# pc_heartypatch.net
KiCad netlist of a schematic drawn in EAGLE
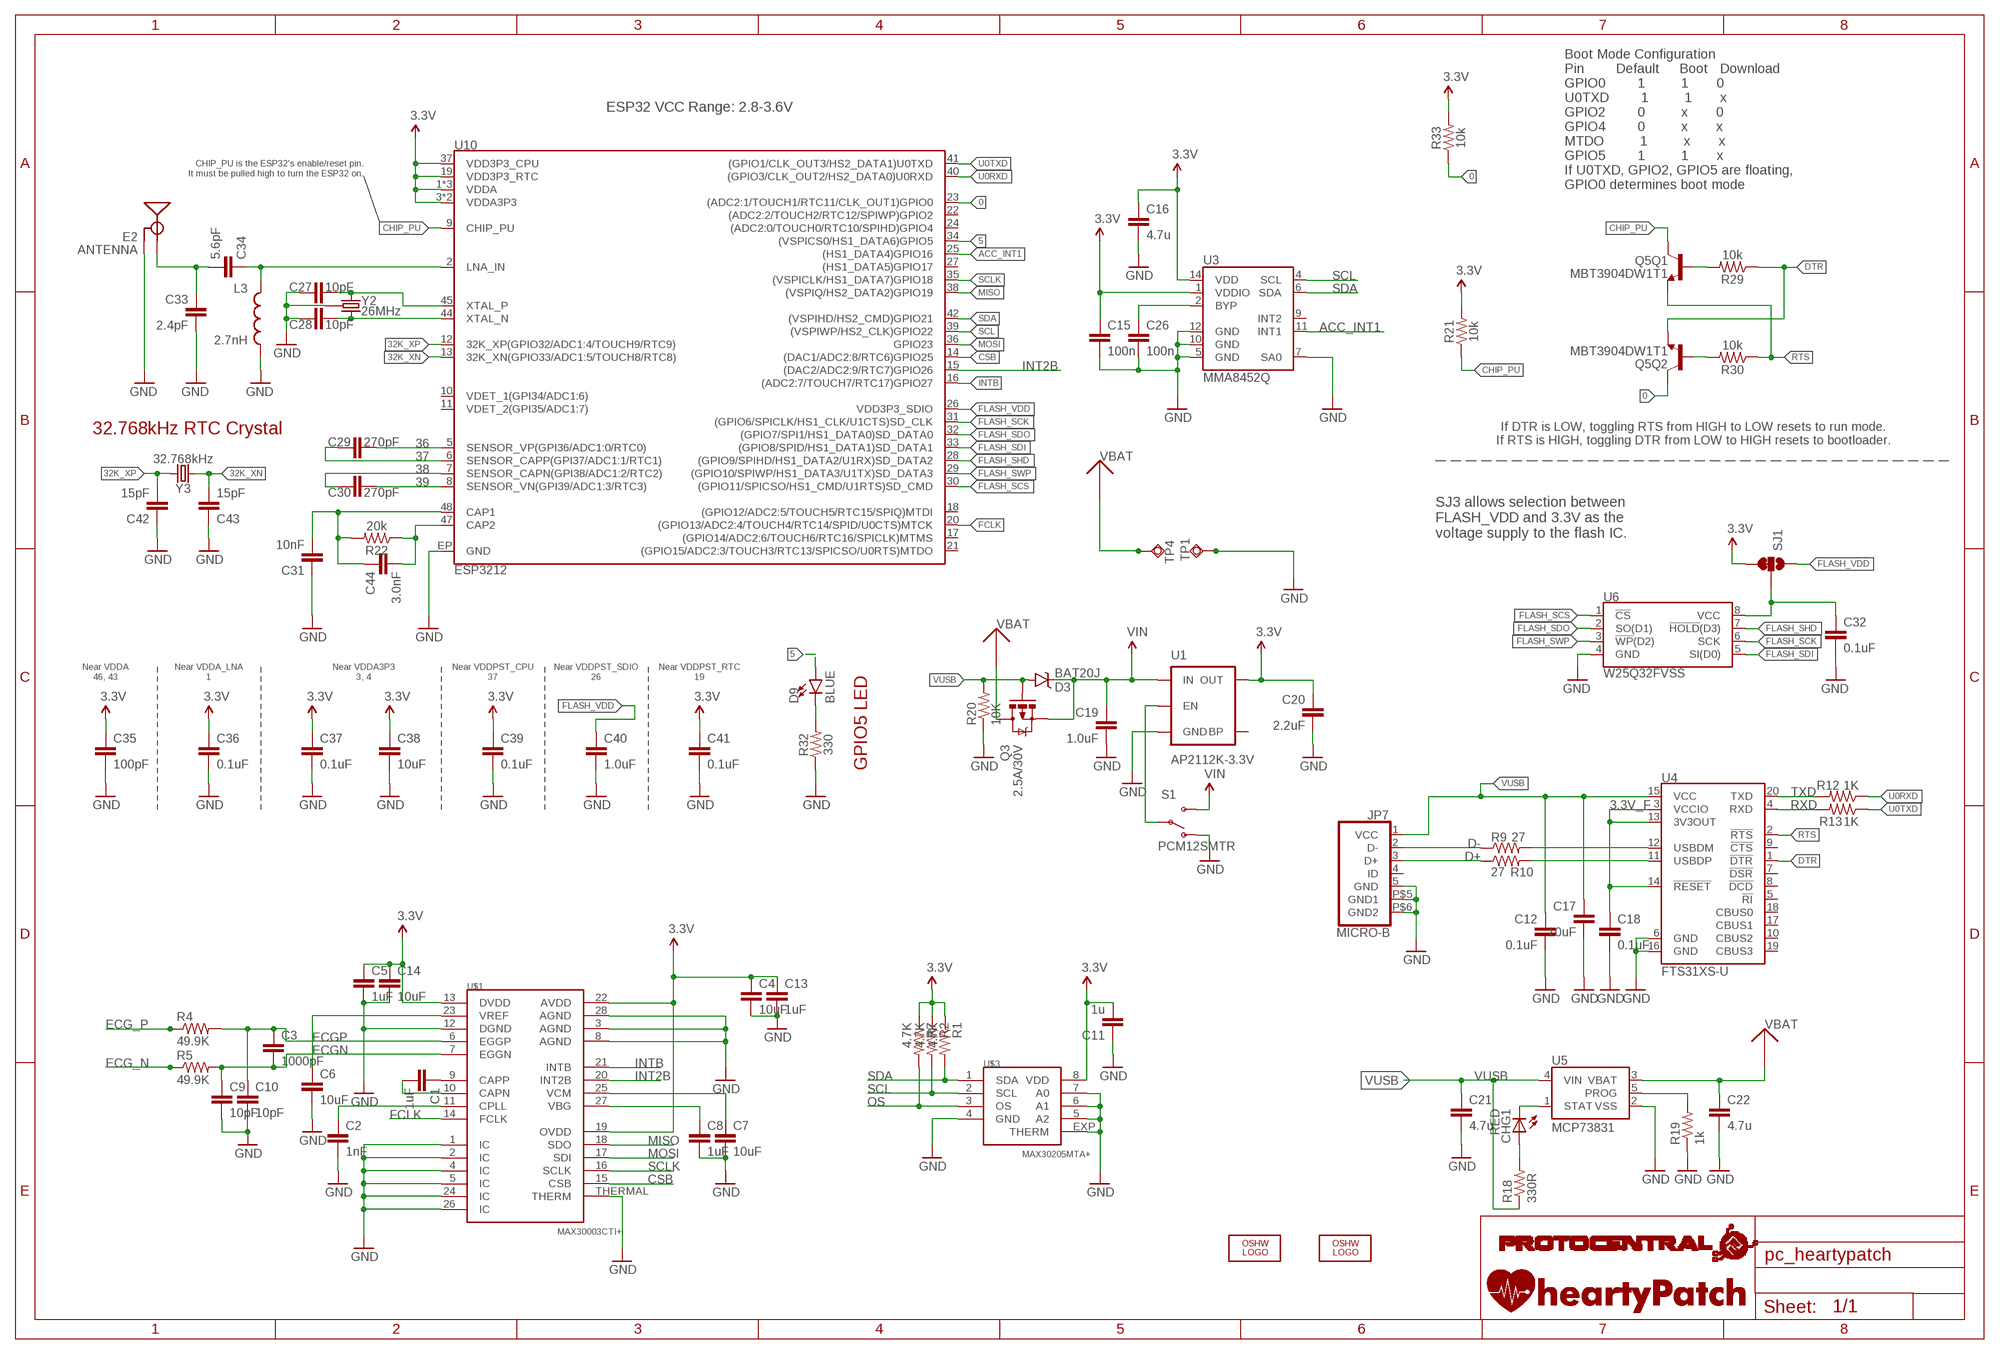
[diagram p0: schematic, sheet 1]

(export (version "E")
  (design (tool "Eeschema 10.0.6"))
  (components
    (comp (ref "C1")
      (value "1uF")
      (footprint "eagle-import:C0603")
      (libsource (lib "eagle-import") (part "C-EUC0603"))
    )
    (comp (ref "C2")
      (value "1nF")
      (footprint "eagle-import:C0603")
      (libsource (lib "eagle-import") (part "C-EUC0603"))
    )
    (comp (ref "C3")
      (value "1000pF")
      (footprint "eagle-import:C0402")
      (libsource (lib "eagle-import") (part "C-EUC0402"))
    )
    (comp (ref "C4")
      (value "10uF")
      (footprint "eagle-import:C0805")
      (libsource (lib "eagle-import") (part "C-EUC0805"))
    )
    (comp (ref "C5")
      (value "1uF")
      (footprint "eagle-import:C0402")
      (libsource (lib "eagle-import") (part "C-EUC0402"))
    )
    (comp (ref "C6")
      (value "10uF")
      (footprint "eagle-import:C0805")
      (libsource (lib "eagle-import") (part "C-EUC0805"))
    )
    (comp (ref "C7")
      (value "10uF")
      (footprint "eagle-import:C0805")
      (libsource (lib "eagle-import") (part "C-EUC0805"))
    )
    (comp (ref "C8")
      (value "1uF")
      (footprint "eagle-import:C0805")
      (libsource (lib "eagle-import") (part "C-EUC0805"))
    )
    (comp (ref "C9")
      (value "10pF")
      (footprint "eagle-import:C0402")
      (libsource (lib "eagle-import") (part "C-EUC0402"))
    )
    (comp (ref "C10")
      (value "10pF")
      (footprint "eagle-import:C0402")
      (libsource (lib "eagle-import") (part "C-EUC0402"))
    )
    (comp (ref "C11")
      (value "1u")
      (footprint "eagle-import:C0805")
      (libsource (lib "eagle-import") (part "C-EUC0805"))
    )
    (comp (ref "C12")
      (value "0.1uF")
      (footprint "eagle-import:C0402")
      (libsource (lib "eagle-import") (part "C-EUC0402"))
    )
    (comp (ref "C13")
      (value "1uF")
      (footprint "eagle-import:C0805")
      (libsource (lib "eagle-import") (part "C-EUC0805"))
    )
    (comp (ref "C14")
      (value "10uF")
      (footprint "eagle-import:C0603")
      (libsource (lib "eagle-import") (part "C-EUC0603"))
    )
    (comp (ref "C15")
      (value "100n")
      (footprint "eagle-import:C0402")
      (libsource (lib "eagle-import") (part "C-EUC0402"))
    )
    (comp (ref "C16")
      (value "4.7u")
      (footprint "eagle-import:C0805")
      (libsource (lib "eagle-import") (part "C-EUC0805"))
    )
    (comp (ref "C17")
      (value "10uF")
      (footprint "eagle-import:C0805")
      (libsource (lib "eagle-import") (part "C-EUC0805"))
    )
    (comp (ref "C18")
      (value "0.1uF")
      (footprint "eagle-import:C0402")
      (libsource (lib "eagle-import") (part "C-EUC0402"))
    )
    (comp (ref "C19")
      (value "1.0uF")
      (footprint "eagle-import:C0402")
      (libsource (lib "eagle-import") (part "C-EUC0402"))
    )
    (comp (ref "C20")
      (value "2.2uF")
      (footprint "eagle-import:0603-CAP@1")
      (libsource (lib "eagle-import") (part "2.2UF-10V-20%(0603)"))
    )
    (comp (ref "C21")
      (value "4.7u")
      (footprint "eagle-import:C0805")
      (libsource (lib "eagle-import") (part "C-EUC0805"))
    )
    (comp (ref "C22")
      (value "4.7u")
      (footprint "eagle-import:C0805")
      (libsource (lib "eagle-import") (part "C-EUC0805"))
    )
    (comp (ref "C26")
      (value "100n")
      (footprint "eagle-import:C0402")
      (libsource (lib "eagle-import") (part "C-EUC0402"))
    )
    (comp (ref "C27")
      (value "10pF")
      (footprint "eagle-import:0603")
      (libsource (lib "eagle-import") (part "10PF-0603-50V-5%"))
    )
    (comp (ref "C28")
      (value "10pF")
      (footprint "eagle-import:0603")
      (libsource (lib "eagle-import") (part "10PF-0603-50V-5%"))
    )
    (comp (ref "C29")
      (value "270pF")
      (footprint "eagle-import:0603")
      (libsource (lib "eagle-import") (part "270PF-50V-5%(0603)"))
    )
    (comp (ref "C30")
      (value "270pF")
      (footprint "eagle-import:0603")
      (libsource (lib "eagle-import") (part "270PF-50V-5%(0603)"))
    )
    (comp (ref "C31")
      (value "10nF")
      (footprint "eagle-import:0603")
      (libsource (lib "eagle-import") (part "10NF-0603-50V-10%"))
    )
    (comp (ref "C32")
      (value "0.1uF")
      (footprint "eagle-import:0402")
      (libsource (lib "eagle-import") (part "0.1UF-0402-16V-10%"))
    )
    (comp (ref "C33")
      (value "2.4pF")
      (footprint "eagle-import:0603")
      (libsource (lib "eagle-import") (part "2.4PF-0603-50V-5%"))
    )
    (comp (ref "C34")
      (value "5.6pF")
      (footprint "eagle-import:0603")
      (libsource (lib "eagle-import") (part "5.6PF-50V-5%(0603)"))
    )
    (comp (ref "C35")
      (value "100pF")
      (footprint "eagle-import:0603")
      (libsource (lib "eagle-import") (part "100PF-0603-50V-5%"))
    )
    (comp (ref "C36")
      (value "0.1uF")
      (footprint "eagle-import:0603")
      (libsource (lib "eagle-import") (part "0.1UF-0603-25V-(+80/-20%)"))
    )
    (comp (ref "C37")
      (value "0.1uF")
      (footprint "eagle-import:0603")
      (libsource (lib "eagle-import") (part "0.1UF-0603-25V-(+80/-20%)"))
    )
    (comp (ref "C38")
      (value "10uF")
      (footprint "eagle-import:0603")
      (libsource (lib "eagle-import") (part "10UF-0603-6.3V-20%"))
    )
    (comp (ref "C39")
      (value "0.1uF")
      (footprint "eagle-import:0402")
      (libsource (lib "eagle-import") (part "0.1UF-0402-16V-10%"))
    )
    (comp (ref "C40")
      (value "1.0uF")
      (footprint "eagle-import:0603")
      (libsource (lib "eagle-import") (part "1.0UF-0603-16V-10%"))
    )
    (comp (ref "C41")
      (value "0.1uF")
      (footprint "eagle-import:0603")
      (libsource (lib "eagle-import") (part "0.1UF-0603-25V-(+80/-20%)"))
    )
    (comp (ref "C42")
      (value "15pF")
      (footprint "eagle-import:0603")
      (libsource (lib "eagle-import") (part "15PF-0603-50V-5%"))
    )
    (comp (ref "C43")
      (value "15pF")
      (footprint "eagle-import:0603")
      (libsource (lib "eagle-import") (part "15PF-0603-50V-5%"))
    )
    (comp (ref "C44")
      (value "3.0nF")
      (footprint "eagle-import:0603")
      (libsource (lib "eagle-import") (part "3.0NF-0603-50V-5%"))
    )
    (comp (ref "CHG1")
      (value "RED")
      (footprint "eagle-import:CHIPLED_0603")
      (libsource (lib "eagle-import") (part "LEDCHIPLED_0603"))
    )
    (comp (ref "D3")
      (value "BAT20J")
      (footprint "eagle-import:SOD-323")
      (libsource (lib "eagle-import") (part "DIODE-SCHOTTKY-BAT20J"))
    )
    (comp (ref "D9")
      (value "BLUE")
      (footprint "eagle-import:LED-0603")
      (libsource (lib "eagle-import") (part "LED-BLUE0603"))
    )
    (comp (ref "E2")
      (value "ANTENNA")
      (footprint "eagle-import:TRACE_ANTENNA_2.4GHZ_25.7MM_TUNED")
      (libsource (lib "eagle-import") (part "ANTENNATRACE-TUNED"))
    )
    (comp (ref "JP7")
      (value "MICRO-B")
      (footprint "eagle-import:MICRO-B")
      (libsource (lib "eagle-import") (part "MICRO-B"))
    )
    (comp (ref "L3")
      (value "2.7nH")
      (footprint "eagle-import:0603")
      (libsource (lib "eagle-import") (part "INDUCTOR0603"))
    )
    (comp (ref "LOGO1")
      (value "OSHW_LOGO_FILLX0200-NT")
      (footprint "eagle-import:OSHW_FILLX200_NOTEXT")
      (libsource (lib "eagle-import") (part "OSHW_LOGO_FILLX0200-NT"))
    )
    (comp (ref "LOGO2")
      (value "OSHW_LOGO_FILLX0200-NT")
      (footprint "eagle-import:OSHW_FILLX200_NOTEXT")
      (libsource (lib "eagle-import") (part "OSHW_LOGO_FILLX0200-NT"))
    )
    (comp (ref "Q3")
      (value "2.5A/30V")
      (footprint "eagle-import:SOT23-3")
      (libsource (lib "eagle-import") (part "MOSFET-PCHANNELDMG2307L"))
    )
    (comp (ref "Q5")
      (value "MBT3904DW1T1")
      (footprint "eagle-import:SC70-6")
      (libsource (lib "eagle-import") (part "MBT3904DW1T1"))
    )
    (comp (ref "R1")
      (value "4.7K")
      (footprint "eagle-import:R0402")
      (libsource (lib "eagle-import") (part "R-US_R0402"))
    )
    (comp (ref "R2")
      (value "4.7K")
      (footprint "eagle-import:R0402")
      (libsource (lib "eagle-import") (part "R-US_R0402"))
    )
    (comp (ref "R4")
      (value "49.9K")
      (footprint "eagle-import:0805")
      (libsource (lib "eagle-import") (part "RESISTOR0805-RES"))
    )
    (comp (ref "R5")
      (value "49.9K")
      (footprint "eagle-import:0805")
      (libsource (lib "eagle-import") (part "RESISTOR0805-RES"))
    )
    (comp (ref "R7")
      (value "4.7K")
      (footprint "eagle-import:R0402")
      (libsource (lib "eagle-import") (part "R-US_R0402"))
    )
    (comp (ref "R9")
      (value "27")
      (footprint "eagle-import:R0402")
      (libsource (lib "eagle-import") (part "R-US_R0402"))
    )
    (comp (ref "R10")
      (value "27")
      (footprint "eagle-import:R0402")
      (libsource (lib "eagle-import") (part "R-US_R0402"))
    )
    (comp (ref "R12")
      (value "1K")
      (footprint "eagle-import:R0402")
      (libsource (lib "eagle-import") (part "R-US_R0402"))
    )
    (comp (ref "R13")
      (value "1K")
      (footprint "eagle-import:R0402")
      (libsource (lib "eagle-import") (part "R-US_R0402"))
    )
    (comp (ref "R18")
      (value "330R")
      (footprint "eagle-import:R0402")
      (libsource (lib "eagle-import") (part "R-US_R0402"))
    )
    (comp (ref "R19")
      (value "1k")
      (footprint "eagle-import:R0402")
      (libsource (lib "eagle-import") (part "R-US_R0402"))
    )
    (comp (ref "R20")
      (value "10K")
      (footprint "eagle-import:R0402")
      (libsource (lib "eagle-import") (part "R-US_R0402"))
    )
    (comp (ref "R21")
      (value "10k")
      (footprint "eagle-import:0603")
      (libsource (lib "eagle-import") (part "10KOHM-1/10W-1%(0603)0603"))
    )
    (comp (ref "R22")
      (value "20k")
      (footprint "eagle-import:0603")
      (libsource (lib "eagle-import") (part "20KOHM-0603-1/10W-1%"))
    )
    (comp (ref "R29")
      (value "10k")
      (footprint "eagle-import:0603")
      (libsource (lib "eagle-import") (part "10KOHM-0603-1/10W-1%"))
    )
    (comp (ref "R30")
      (value "10k")
      (footprint "eagle-import:0603")
      (libsource (lib "eagle-import") (part "10KOHM-0603-1/10W-1%"))
    )
    (comp (ref "R32")
      (value "330")
      (footprint "eagle-import:0603")
      (libsource (lib "eagle-import") (part "330OHM1/10W1%(0603)"))
    )
    (comp (ref "R33")
      (value "10k")
      (footprint "eagle-import:0603")
      (libsource (lib "eagle-import") (part "10KOHM-1/10W-1%(0603)0603"))
    )
    (comp (ref "S1")
      (value "PCM12SMTR")
      (footprint "eagle-import:SWITCH-SPST-SMD-A")
      (libsource (lib "eagle-import") (part "SWITCH-SPDT-SMD-A"))
    )
    (comp (ref "SJ1")
      (value "JUMPER-PAD-3-2OF3_NC_BY_TRACE_SMALL")
      (footprint "eagle-import:PAD-JUMPER-3-2OF3_NC_BY_TRACE_YES_SILK_FULL_BOX")
      (libsource (lib "eagle-import") (part "JUMPER-PAD-3-2OF3_NC_BY_TRACE_SMALL"))
    )
    (comp (ref "TP1")
      (value "TPSQTP20SQ")
      (footprint "eagle-import:TP20SQ")
      (libsource (lib "eagle-import") (part "TPSQTP20SQ"))
    )
    (comp (ref "TP4")
      (value "TPSQTP20SQ")
      (footprint "eagle-import:TP20SQ")
      (libsource (lib "eagle-import") (part "TPSQTP20SQ"))
    )
    (comp (ref "U$1")
      (value "MAX30003CTI+")
      (footprint "eagle-import:QFN-28")
      (libsource (lib "eagle-import") (part "MAX30003"))
    )
    (comp (ref "U$3")
      (value "MAX30205MTA+")
      (footprint "eagle-import:TDFN-08")
      (libsource (lib "eagle-import") (part "MAX30205MTA+"))
    )
    (comp (ref "U$8")
      (value "HEARTYPATCHHEART")
      (footprint "eagle-import:HEARTYPATCH")
      (libsource (lib "eagle-import") (part "HEARTYPATCHHEART"))
    )
    (comp (ref "U$9")
      (value "PROTY_LOGO_WITH_TEXT")
      (footprint "eagle-import:PROTY_WITH_TEXT")
      (libsource (lib "eagle-import") (part "PROTY_LOGO_WITH_TEXT"))
    )
    (comp (ref "U1")
      (value "AP2112K-3.3V")
      (footprint "eagle-import:SOT23-5")
      (libsource (lib "eagle-import") (part "V_REG_LDOSMD"))
    )
    (comp (ref "U3")
      (value "MMA8452Q")
      (footprint "eagle-import:QFN-16_0.5MM")
      (libsource (lib "eagle-import") (part "MMA8452Q"))
    )
    (comp (ref "U4")
      (value "FTS31XS-U")
      (footprint "eagle-import:SSOP20_L")
      (libsource (lib "eagle-import") (part "FT231XS"))
    )
    (comp (ref "U5")
      (value "MCP73831")
      (footprint "eagle-import:SOT23-5")
      (libsource (lib "eagle-import") (part "MCP73831"))
    )
    (comp (ref "U6")
      (value "W25Q32FVSS")
      (footprint "eagle-import:SOIC-8")
      (libsource (lib "eagle-import") (part "W25Q32FVSS"))
    )
    (comp (ref "U10")
      (value "ESP3212")
      (footprint "eagle-import:QFN48-0.4MM")
      (libsource (lib "eagle-import") (part "ESP3212"))
    )
    (comp (ref "Y2")
      (value "26MHz")
      (footprint "eagle-import:CRYSTAL-SMD-3.2X2.5")
      (libsource (lib "eagle-import") (part "CRYSTAL-GROUNDED3.2X2.5"))
    )
    (comp (ref "Y3")
      (value "32.768kHz")
      (footprint "eagle-import:CRYSTAL-SMD-3.2X1.5MM")
      (libsource (lib "eagle-import") (part "CRYSTAL-32.768KHZSMD-3.2X1.5"))
    )
  )
  (nets
    (net (code "1") (name "/3.3V_F") (class "Default")
      (node (ref "C18") (pin "1") (pinfunction "1_1") (pintype "passive"))
      (node (ref "U4") (pin "13") (pinfunction "3V3OUT_13") (pintype "bidirectional"))
      (node (ref "U4") (pin "14") (pinfunction "~{RESET}_14") (pintype "bidirectional"))
      (node (ref "U4") (pin "3") (pinfunction "VCCIO_3") (pintype "bidirectional"))
    )
    (net (code "2") (name "/36") (class "Default")
      (node (ref "C29") (pin "2") (pinfunction "2_2") (pintype "passive"))
      (node (ref "U10") (pin "5") (pinfunction "SENSOR_VP(GPI36/ADC1:0/RTC0)_5") (pintype "bidirectional"))
    )
    (net (code "3") (name "/37") (class "Default")
      (node (ref "C29") (pin "1") (pinfunction "1_1") (pintype "passive"))
      (node (ref "U10") (pin "6") (pinfunction "SENSOR_CAPP(GPI37/ADC1:1/RTC1)_6") (pintype "bidirectional"))
    )
    (net (code "4") (name "/38") (class "Default")
      (node (ref "C30") (pin "1") (pinfunction "1_1") (pintype "passive"))
      (node (ref "U10") (pin "7") (pinfunction "SENSOR_CAPN(GPI38/ADC1:2/RTC2)_7") (pintype "bidirectional"))
    )
    (net (code "5") (name "/39") (class "Default")
      (node (ref "C30") (pin "2") (pinfunction "2_2") (pintype "passive"))
      (node (ref "U10") (pin "8") (pinfunction "SENSOR_VN(GPI39/ADC1:3/RTC3)_8") (pintype "bidirectional"))
    )
    (net (code "6") (name "/D+") (class "Default")
      (node (ref "JP7") (pin "3") (pinfunction "D+_3") (pintype "bidirectional"))
      (node (ref "R10") (pin "1") (pinfunction "1_1") (pintype "passive"))
    )
    (net (code "7") (name "/D-") (class "Default")
      (node (ref "JP7") (pin "2") (pinfunction "D-_2") (pintype "bidirectional"))
      (node (ref "R9") (pin "1") (pinfunction "1_1") (pintype "passive"))
    )
    (net (code "8") (name "/ECGN") (class "Default")
      (node (ref "C3") (pin "2") (pinfunction "2_2") (pintype "passive"))
      (node (ref "C9") (pin "1") (pinfunction "1_1") (pintype "passive"))
      (node (ref "R5") (pin "2") (pinfunction "2_2") (pintype "passive"))
      (node (ref "U$1") (pin "7") (pinfunction "EGGN_7") (pintype "bidirectional"))
    )
    (net (code "9") (name "/ECGP") (class "Default")
      (node (ref "C10") (pin "1") (pinfunction "1_1") (pintype "passive"))
      (node (ref "C3") (pin "1") (pinfunction "1_1") (pintype "passive"))
      (node (ref "R4") (pin "2") (pinfunction "2_2") (pintype "passive"))
      (node (ref "U$1") (pin "6") (pinfunction "EGGP_6") (pintype "bidirectional"))
    )
    (net (code "10") (name "/ECG_N") (class "Default")
      (node (ref "R5") (pin "1") (pinfunction "1_1") (pintype "passive"))
    )
    (net (code "11") (name "/ECG_P") (class "Default")
      (node (ref "R4") (pin "1") (pinfunction "1_1") (pintype "passive"))
    )
    (net (code "12") (name "/INT2B") (class "Default")
      (node (ref "U$1") (pin "20") (pinfunction "INT2B_20") (pintype "bidirectional"))
      (node (ref "U10") (pin "15") (pinfunction "(DAC2/ADC2:9/RTC7)GPIO26_15") (pintype "bidirectional"))
    )
    (net (code "13") (name "/OS") (class "Default")
      (node (ref "R7") (pin "2") (pinfunction "2_2") (pintype "passive"))
      (node (ref "U$3") (pin "3") (pinfunction "OS_3") (pintype "bidirectional"))
    )
    (net (code "14") (name "/RXD") (class "Default")
      (node (ref "R13") (pin "2") (pinfunction "2_2") (pintype "passive"))
      (node (ref "U4") (pin "4") (pinfunction "RXD_4") (pintype "bidirectional"))
    )
    (net (code "15") (name "/TXD") (class "Default")
      (node (ref "R12") (pin "2") (pinfunction "2_2") (pintype "passive"))
      (node (ref "U4") (pin "20") (pinfunction "TXD_20") (pintype "bidirectional"))
    )
    (net (code "16") (name "0") (class "Default")
      (node (ref "Q5") (pin "6") (pinfunction "C_6") (pintype "passive"))
      (node (ref "R33") (pin "1") (pinfunction "1_1") (pintype "passive"))
      (node (ref "U10") (pin "23") (pinfunction "(ADC2:1/TOUCH1/RTC11/CLK_OUT1)GPIO0_23") (pintype "bidirectional"))
    )
    (net (code "17") (name "3.3V") (class "Default")
      (node (ref "C11") (pin "2") (pinfunction "2_2") (pintype "passive"))
      (node (ref "C13") (pin "1") (pinfunction "1_1") (pintype "passive"))
      (node (ref "C14") (pin "1") (pinfunction "1_1") (pintype "passive"))
      (node (ref "C15") (pin "1") (pinfunction "1_1") (pintype "passive"))
      (node (ref "C16") (pin "1") (pinfunction "1_1") (pintype "passive"))
      (node (ref "C20") (pin "1") (pinfunction "1_1") (pintype "passive"))
      (node (ref "C35") (pin "1") (pinfunction "1_1") (pintype "passive"))
      (node (ref "C36") (pin "1") (pinfunction "1_1") (pintype "passive"))
      (node (ref "C37") (pin "1") (pinfunction "1_1") (pintype "passive"))
      (node (ref "C38") (pin "1") (pinfunction "1_1") (pintype "passive"))
      (node (ref "C39") (pin "1") (pinfunction "1_1") (pintype "passive"))
      (node (ref "C4") (pin "1") (pinfunction "1_1") (pintype "passive"))
      (node (ref "C41") (pin "1") (pinfunction "1_1") (pintype "passive"))
      (node (ref "C5") (pin "1") (pinfunction "1_1") (pintype "passive"))
      (node (ref "R1") (pin "1") (pinfunction "1_1") (pintype "passive"))
      (node (ref "R2") (pin "1") (pinfunction "1_1") (pintype "passive"))
      (node (ref "R21") (pin "2") (pinfunction "2_2") (pintype "passive"))
      (node (ref "R33") (pin "2") (pinfunction "2_2") (pintype "passive"))
      (node (ref "R7") (pin "1") (pinfunction "1_1") (pintype "passive"))
      (node (ref "SJ1") (pin "3") (pinfunction "3_3") (pintype "passive"))
      (node (ref "U$1") (pin "13") (pinfunction "DVDD_13") (pintype "bidirectional"))
      (node (ref "U$1") (pin "19") (pinfunction "OVDD_19") (pintype "bidirectional"))
      (node (ref "U$1") (pin "22") (pinfunction "AVDD_22") (pintype "bidirectional"))
      (node (ref "U$3") (pin "8") (pinfunction "VDD_8") (pintype "bidirectional"))
      (node (ref "U1") (pin "5") (pinfunction "OUT_5") (pintype "passive"))
      (node (ref "U10") (pin "1") (pinfunction "VDDA_1") (pintype "bidirectional"))
      (node (ref "U10") (pin "19") (pinfunction "VDD3P3_RTC_19") (pintype "bidirectional"))
      (node (ref "U10") (pin "3") (pinfunction "VDDA3P3_3") (pintype "bidirectional"))
      (node (ref "U10") (pin "37") (pinfunction "VDD3P3_CPU_37") (pintype "bidirectional"))
      (node (ref "U10") (pin "4") (pinfunction "VDDA3P3_4") (pintype "bidirectional"))
      (node (ref "U10") (pin "43") (pinfunction "VDDA_43") (pintype "bidirectional"))
      (node (ref "U10") (pin "46") (pinfunction "VDDA_46") (pintype "bidirectional"))
      (node (ref "U3") (pin "1") (pinfunction "VDDIO_1") (pintype "bidirectional"))
      (node (ref "U3") (pin "14") (pinfunction "VDD_14") (pintype "bidirectional"))
    )
    (net (code "18") (name "5") (class "Default")
      (node (ref "D9") (pin "A") (pinfunction "A_A") (pintype "passive"))
      (node (ref "U10") (pin "34") (pinfunction "(VSPICS0/HS1_DATA6)GPIO5_34") (pintype "bidirectional"))
    )
    (net (code "19") (name "32K_XN") (class "Default")
      (node (ref "C43") (pin "2") (pinfunction "2_2") (pintype "passive"))
      (node (ref "U10") (pin "13") (pinfunction "32K_XN(GPIO33/ADC1:5/TOUCH8/RTC8)_13") (pintype "bidirectional"))
      (node (ref "Y3") (pin "P$2") (pinfunction "2_P$2") (pintype "passive"))
    )
    (net (code "20") (name "32K_XP") (class "Default")
      (node (ref "C42") (pin "2") (pinfunction "2_2") (pintype "passive"))
      (node (ref "U10") (pin "12") (pinfunction "32K_XP(GPIO32/ADC1:4/TOUCH9/RTC9)_12") (pintype "bidirectional"))
      (node (ref "Y3") (pin "P$1") (pinfunction "1_P$1") (pintype "passive"))
    )
    (net (code "21") (name "ACC_INT1") (class "Default")
      (node (ref "U10") (pin "25") (pinfunction "(HS1_DATA4)GPIO16_25") (pintype "bidirectional"))
      (node (ref "U3") (pin "11") (pinfunction "INT1_11") (pintype "bidirectional"))
    )
    (net (code "22") (name "CHIP_PU") (class "Default")
      (node (ref "Q5") (pin "3") (pinfunction "C_3") (pintype "passive"))
      (node (ref "R21") (pin "1") (pinfunction "1_1") (pintype "passive"))
      (node (ref "U10") (pin "9") (pinfunction "CHIP_PU_9") (pintype "bidirectional"))
    )
    (net (code "23") (name "CSB") (class "Default")
      (node (ref "U$1") (pin "15") (pinfunction "CSB_15") (pintype "bidirectional"))
      (node (ref "U10") (pin "14") (pinfunction "(DAC1/ADC2:8/RTC6)GPIO25_14") (pintype "bidirectional"))
    )
    (net (code "24") (name "DTR") (class "Default")
      (node (ref "Q5") (pin "1") (pinfunction "E_1") (pintype "passive"))
      (node (ref "R29") (pin "1") (pinfunction "1_1") (pintype "passive"))
      (node (ref "U4") (pin "1") (pinfunction "~{DTR}_1") (pintype "bidirectional"))
    )
    (net (code "25") (name "FCLK") (class "Default")
      (node (ref "U$1") (pin "14") (pinfunction "FCLK_14") (pintype "bidirectional"))
      (node (ref "U10") (pin "20") (pinfunction "(GPIO13/ADC2:4/TOUCH4/RTC14/SPID/U0CTS)MTCK_20") (pintype "bidirectional"))
    )
    (net (code "26") (name "FLASH_SCK") (class "Default")
      (node (ref "U10") (pin "31") (pinfunction "(GPIO6/SPICLK/HS1_CLK/U1CTS)SD_CLK_31") (pintype "bidirectional"))
      (node (ref "U6") (pin "6") (pinfunction "SCK_6") (pintype "bidirectional"))
    )
    (net (code "27") (name "FLASH_SCS") (class "Default")
      (node (ref "U10") (pin "30") (pinfunction "(GPIO11/SPICSO/HS1_CMD/U1RTS)SD_CMD_30") (pintype "bidirectional"))
      (node (ref "U6") (pin "1") (pinfunction "~{CS}_1") (pintype "bidirectional"))
    )
    (net (code "28") (name "FLASH_SDI") (class "Default")
      (node (ref "U10") (pin "33") (pinfunction "(GPIO8/SPID/HS1_DATA1)SD_DATA1_33") (pintype "bidirectional"))
      (node (ref "U6") (pin "5") (pinfunction "SI(D0)_5") (pintype "bidirectional"))
    )
    (net (code "29") (name "FLASH_SDO") (class "Default")
      (node (ref "U10") (pin "32") (pinfunction "(GPIO7/SPI1/HS1_DATA0)SD_DATA0_32") (pintype "bidirectional"))
      (node (ref "U6") (pin "2") (pinfunction "SO(D1)_2") (pintype "bidirectional"))
    )
    (net (code "30") (name "FLASH_SHD") (class "Default")
      (node (ref "U10") (pin "28") (pinfunction "(GPIO9/SPIHD/HS1_DATA2/U1RX)SD_DATA2_28") (pintype "bidirectional"))
      (node (ref "U6") (pin "7") (pinfunction "~{HOLD}(D3)_7") (pintype "bidirectional"))
    )
    (net (code "31") (name "FLASH_SWP") (class "Default")
      (node (ref "U10") (pin "29") (pinfunction "(GPIO10/SPIWP/HS1_DATA3/U1TX)SD_DATA3_29") (pintype "bidirectional"))
      (node (ref "U6") (pin "3") (pinfunction "~{WP}(D2)_3") (pintype "bidirectional"))
    )
    (net (code "32") (name "FLASH_VDD") (class "Default")
      (node (ref "C40") (pin "1") (pinfunction "1_1") (pintype "passive"))
      (node (ref "SJ1") (pin "1") (pinfunction "1_1") (pintype "passive"))
      (node (ref "U10") (pin "26") (pinfunction "VDD3P3_SDIO_26") (pintype "bidirectional"))
    )
    (net (code "33") (name "GND") (class "Default")
      (node (ref "C10") (pin "2") (pinfunction "2_2") (pintype "passive"))
      (node (ref "C11") (pin "1") (pinfunction "1_1") (pintype "passive"))
      (node (ref "C12") (pin "2") (pinfunction "2_2") (pintype "passive"))
      (node (ref "C13") (pin "2") (pinfunction "2_2") (pintype "passive"))
      (node (ref "C14") (pin "2") (pinfunction "2_2") (pintype "passive"))
      (node (ref "C15") (pin "2") (pinfunction "2_2") (pintype "passive"))
      (node (ref "C16") (pin "2") (pinfunction "2_2") (pintype "passive"))
      (node (ref "C17") (pin "2") (pinfunction "2_2") (pintype "passive"))
      (node (ref "C18") (pin "2") (pinfunction "2_2") (pintype "passive"))
      (node (ref "C19") (pin "2") (pinfunction "2_2") (pintype "passive"))
      (node (ref "C2") (pin "2") (pinfunction "2_2") (pintype "passive"))
      (node (ref "C20") (pin "2") (pinfunction "2_2") (pintype "passive"))
      (node (ref "C21") (pin "2") (pinfunction "2_2") (pintype "passive"))
      (node (ref "C22") (pin "2") (pinfunction "2_2") (pintype "passive"))
      (node (ref "C26") (pin "2") (pinfunction "2_2") (pintype "passive"))
      (node (ref "C27") (pin "1") (pinfunction "1_1") (pintype "passive"))
      (node (ref "C28") (pin "1") (pinfunction "1_1") (pintype "passive"))
      (node (ref "C31") (pin "1") (pinfunction "1_1") (pintype "passive"))
      (node (ref "C32") (pin "2") (pinfunction "2_2") (pintype "passive"))
      (node (ref "C33") (pin "2") (pinfunction "2_2") (pintype "passive"))
      (node (ref "C35") (pin "2") (pinfunction "2_2") (pintype "passive"))
      (node (ref "C36") (pin "2") (pinfunction "2_2") (pintype "passive"))
      (node (ref "C37") (pin "2") (pinfunction "2_2") (pintype "passive"))
      (node (ref "C38") (pin "2") (pinfunction "2_2") (pintype "passive"))
      (node (ref "C39") (pin "2") (pinfunction "2_2") (pintype "passive"))
      (node (ref "C4") (pin "2") (pinfunction "2_2") (pintype "passive"))
      (node (ref "C40") (pin "2") (pinfunction "2_2") (pintype "passive"))
      (node (ref "C41") (pin "2") (pinfunction "2_2") (pintype "passive"))
      (node (ref "C42") (pin "1") (pinfunction "1_1") (pintype "passive"))
      (node (ref "C43") (pin "1") (pinfunction "1_1") (pintype "passive"))
      (node (ref "C5") (pin "2") (pinfunction "2_2") (pintype "passive"))
      (node (ref "C6") (pin "2") (pinfunction "2_2") (pintype "passive"))
      (node (ref "C7") (pin "2") (pinfunction "2_2") (pintype "passive"))
      (node (ref "C8") (pin "2") (pinfunction "2_2") (pintype "passive"))
      (node (ref "C9") (pin "2") (pinfunction "2_2") (pintype "passive"))
      (node (ref "E2") (pin "GND") (pinfunction "GND_GND") (pintype "bidirectional"))
      (node (ref "E2") (pin "GND2") (pinfunction "GND_GND2") (pintype "bidirectional"))
      (node (ref "JP7") (pin "5") (pinfunction "GND_5") (pintype "bidirectional"))
      (node (ref "JP7") (pin "P$5") (pinfunction "GND1_P$5") (pintype "bidirectional"))
      (node (ref "JP7") (pin "P$6") (pinfunction "GND2_P$6") (pintype "bidirectional"))
      (node (ref "L3") (pin "2") (pinfunction "2_2") (pintype "passive"))
      (node (ref "R19") (pin "1") (pinfunction "1_1") (pintype "passive"))
      (node (ref "R20") (pin "1") (pinfunction "1_1") (pintype "passive"))
      (node (ref "R32") (pin "1") (pinfunction "1_1") (pintype "passive"))
      (node (ref "S1") (pin "1") (pinfunction "O_1") (pintype "passive"))
      (node (ref "TP1") (pin "TP") (pinfunction "TP_TP") (pintype "input"))
      (node (ref "U$1") (pin "1") (pinfunction "IC_1") (pintype "bidirectional"))
      (node (ref "U$1") (pin "12") (pinfunction "DGND_12") (pintype "bidirectional"))
      (node (ref "U$1") (pin "2") (pinfunction "IC_2") (pintype "bidirectional"))
      (node (ref "U$1") (pin "24") (pinfunction "IC_24") (pintype "bidirectional"))
      (node (ref "U$1") (pin "26") (pinfunction "IC_26") (pintype "bidirectional"))
      (node (ref "U$1") (pin "28") (pinfunction "AGND_28") (pintype "bidirectional"))
      (node (ref "U$1") (pin "3") (pinfunction "AGND_3") (pintype "bidirectional"))
      (node (ref "U$1") (pin "4") (pinfunction "IC_4") (pintype "bidirectional"))
      (node (ref "U$1") (pin "5") (pinfunction "IC_5") (pintype "bidirectional"))
      (node (ref "U$1") (pin "8") (pinfunction "AGND_8") (pintype "bidirectional"))
      (node (ref "U$1") (pin "THERMAL") (pinfunction "THERM_THERMAL") (pintype "bidirectional"))
      (node (ref "U$3") (pin "4") (pinfunction "GND_4") (pintype "bidirectional"))
      (node (ref "U$3") (pin "5") (pinfunction "A2_5") (pintype "bidirectional"))
      (node (ref "U$3") (pin "6") (pinfunction "A1_6") (pintype "bidirectional"))
      (node (ref "U$3") (pin "7") (pinfunction "A0_7") (pintype "bidirectional"))
      (node (ref "U$3") (pin "EXP") (pinfunction "THERM_EXP") (pintype "bidirectional"))
      (node (ref "U1") (pin "2") (pinfunction "GND_2") (pintype "input"))
      (node (ref "U10") (pin "EP") (pinfunction "GND_EP") (pintype "bidirectional"))
      (node (ref "U3") (pin "10") (pinfunction "GND_10") (pintype "bidirectional"))
      (node (ref "U3") (pin "12") (pinfunction "GND_12") (pintype "bidirectional"))
      (node (ref "U3") (pin "5") (pinfunction "GND_5") (pintype "bidirectional"))
      (node (ref "U3") (pin "7") (pinfunction "SA0_7") (pintype "bidirectional"))
      (node (ref "U4") (pin "16") (pinfunction "GND_16") (pintype "bidirectional"))
      (node (ref "U4") (pin "6") (pinfunction "GND_6") (pintype "bidirectional"))
      (node (ref "U5") (pin "2") (pinfunction "VSS_2") (pintype "power_in"))
      (node (ref "U6") (pin "4") (pinfunction "GND_4") (pintype "bidirectional"))
      (node (ref "Y2") (pin "2") (pinfunction "GND_2") (pintype "passive"))
      (node (ref "Y2") (pin "4") (pinfunction "GND_4") (pintype "passive"))
    )
    (net (code "34") (name "INTB") (class "Default")
      (node (ref "U$1") (pin "21") (pinfunction "INTB_21") (pintype "bidirectional"))
      (node (ref "U10") (pin "16") (pinfunction "(ADC2:7/TOUCH7/RTC17)GPIO27_16") (pintype "bidirectional"))
    )
    (net (code "35") (name "MISO") (class "Default")
      (node (ref "U$1") (pin "18") (pinfunction "SDO_18") (pintype "bidirectional"))
      (node (ref "U10") (pin "38") (pinfunction "(VSPIQ/HS2_DATA2)GPIO19_38") (pintype "bidirectional"))
    )
    (net (code "36") (name "MOSI") (class "Default")
      (node (ref "U$1") (pin "17") (pinfunction "SDI_17") (pintype "bidirectional"))
      (node (ref "U10") (pin "36") (pinfunction "GPIO23_36") (pintype "bidirectional"))
    )
    (net (code "37") (name "Net-(CHG1-PadA)") (class "Default")
      (node (ref "CHG1") (pin "A") (pinfunction "A_A") (pintype "passive"))
      (node (ref "R18") (pin "2") (pinfunction "2_2") (pintype "passive"))
    )
    (net (code "38") (name "Net-(D9-PadC)") (class "Default")
      (node (ref "D9") (pin "C") (pinfunction "C_C") (pintype "passive"))
      (node (ref "R32") (pin "2") (pinfunction "2_2") (pintype "passive"))
    )
    (net (code "39") (name "Net-(E2-SIGNAL)") (class "Default")
      (node (ref "C33") (pin "1") (pinfunction "1_1") (pintype "passive"))
      (node (ref "C34") (pin "2") (pinfunction "2_2") (pintype "passive"))
      (node (ref "E2") (pin "ANT") (pinfunction "SIGNAL_ANT") (pintype "bidirectional"))
    )
    (net (code "40") (name "Net-(Q5A-B)") (class "Default")
      (node (ref "Q5") (pin "5") (pinfunction "B_5") (pintype "passive"))
      (node (ref "R29") (pin "2") (pinfunction "2_2") (pintype "passive"))
    )
    (net (code "41") (name "Net-(Q5B-B)") (class "Default")
      (node (ref "Q5") (pin "2") (pinfunction "B_2") (pintype "passive"))
      (node (ref "R30") (pin "2") (pinfunction "2_2") (pintype "passive"))
    )
    (net (code "42") (name "Net-(S1-P)") (class "Default")
      (node (ref "S1") (pin "2") (pinfunction "P_2") (pintype "passive"))
      (node (ref "U1") (pin "3") (pinfunction "EN_3") (pintype "input"))
    )
    (net (code "43") (name "Net-(U$1-CAPN)") (class "Default")
      (node (ref "C1") (pin "2") (pinfunction "2_2") (pintype "passive"))
      (node (ref "U$1") (pin "10") (pinfunction "CAPN_10") (pintype "bidirectional"))
    )
    (net (code "44") (name "Net-(U$1-CAPP)") (class "Default")
      (node (ref "C1") (pin "1") (pinfunction "1_1") (pintype "passive"))
      (node (ref "U$1") (pin "9") (pinfunction "CAPP_9") (pintype "bidirectional"))
    )
    (net (code "45") (name "Net-(U$1-CPLL)") (class "Default")
      (node (ref "C2") (pin "1") (pinfunction "1_1") (pintype "passive"))
      (node (ref "U$1") (pin "11") (pinfunction "CPLL_11") (pintype "bidirectional"))
    )
    (net (code "46") (name "Net-(U$1-VBG)") (class "Default")
      (node (ref "C8") (pin "1") (pinfunction "1_1") (pintype "passive"))
      (node (ref "U$1") (pin "27") (pinfunction "VBG_27") (pintype "bidirectional"))
    )
    (net (code "47") (name "Net-(U$1-VCM)") (class "Default")
      (node (ref "C7") (pin "1") (pinfunction "1_1") (pintype "passive"))
      (node (ref "U$1") (pin "25") (pinfunction "VCM_25") (pintype "bidirectional"))
    )
    (net (code "48") (name "Net-(U$1-VREF)") (class "Default")
      (node (ref "C6") (pin "1") (pinfunction "1_1") (pintype "passive"))
      (node (ref "U$1") (pin "23") (pinfunction "VREF_23") (pintype "bidirectional"))
    )
    (net (code "49") (name "Net-(U3-BYP)") (class "Default")
      (node (ref "C26") (pin "1") (pinfunction "1_1") (pintype "passive"))
      (node (ref "U3") (pin "2") (pinfunction "BYP_2") (pintype "bidirectional"))
    )
    (net (code "50") (name "Net-(U4-USBDM)") (class "Default")
      (node (ref "R9") (pin "2") (pinfunction "2_2") (pintype "passive"))
      (node (ref "U4") (pin "12") (pinfunction "USBDM_12") (pintype "bidirectional"))
    )
    (net (code "51") (name "Net-(U4-USBDP)") (class "Default")
      (node (ref "R10") (pin "2") (pinfunction "2_2") (pintype "passive"))
      (node (ref "U4") (pin "11") (pinfunction "USBDP_11") (pintype "bidirectional"))
    )
    (net (code "52") (name "Net-(U5-PROG)") (class "Default")
      (node (ref "R19") (pin "2") (pinfunction "2_2") (pintype "passive"))
      (node (ref "U5") (pin "5") (pinfunction "PROG_5") (pintype "input"))
    )
    (net (code "53") (name "Net-(U5-STAT)") (class "Default")
      (node (ref "CHG1") (pin "C") (pinfunction "C_C") (pintype "passive"))
      (node (ref "U5") (pin "1") (pinfunction "STAT_1") (pintype "output"))
    )
    (net (code "54") (name "Net-(U6-VCC)") (class "Default")
      (node (ref "C32") (pin "1") (pinfunction "1_1") (pintype "passive"))
      (node (ref "SJ1") (pin "2") (pinfunction "2_2") (pintype "passive"))
      (node (ref "U6") (pin "8") (pinfunction "VCC_8") (pintype "bidirectional"))
    )
    (net (code "55") (name "Net-(U10-CAP1)") (class "Default")
      (node (ref "C31") (pin "2") (pinfunction "2_2") (pintype "passive"))
      (node (ref "C44") (pin "1") (pinfunction "1_1") (pintype "passive"))
      (node (ref "R22") (pin "2") (pinfunction "2_2") (pintype "passive"))
      (node (ref "U10") (pin "48") (pinfunction "CAP1_48") (pintype "bidirectional"))
    )
    (net (code "56") (name "Net-(U10-CAP2)") (class "Default")
      (node (ref "C44") (pin "2") (pinfunction "2_2") (pintype "passive"))
      (node (ref "R22") (pin "1") (pinfunction "1_1") (pintype "passive"))
      (node (ref "U10") (pin "47") (pinfunction "CAP2_47") (pintype "bidirectional"))
    )
    (net (code "57") (name "Net-(U10-LNA_IN)") (class "Default")
      (node (ref "C34") (pin "1") (pinfunction "1_1") (pintype "passive"))
      (node (ref "L3") (pin "1") (pinfunction "1_1") (pintype "passive"))
      (node (ref "U10") (pin "2") (pinfunction "LNA_IN_2") (pintype "bidirectional"))
    )
    (net (code "58") (name "Net-(U10-XTAL_N)") (class "Default")
      (node (ref "C28") (pin "2") (pinfunction "2_2") (pintype "passive"))
      (node (ref "U10") (pin "44") (pinfunction "XTAL_N_44") (pintype "bidirectional"))
      (node (ref "Y2") (pin "3") (pinfunction "2_3") (pintype "passive"))
    )
    (net (code "59") (name "Net-(U10-XTAL_P)") (class "Default")
      (node (ref "C27") (pin "2") (pinfunction "2_2") (pintype "passive"))
      (node (ref "U10") (pin "45") (pinfunction "XTAL_P_45") (pintype "bidirectional"))
      (node (ref "Y2") (pin "1") (pinfunction "1_1") (pintype "passive"))
    )
    (net (code "60") (name "RTS") (class "Default")
      (node (ref "Q5") (pin "4") (pinfunction "E_4") (pintype "passive"))
      (node (ref "R30") (pin "1") (pinfunction "1_1") (pintype "passive"))
      (node (ref "U4") (pin "2") (pinfunction "~{RTS}_2") (pintype "bidirectional"))
    )
    (net (code "61") (name "SCL") (class "Default")
      (node (ref "R2") (pin "2") (pinfunction "2_2") (pintype "passive"))
      (node (ref "U$3") (pin "2") (pinfunction "SCL_2") (pintype "bidirectional"))
      (node (ref "U10") (pin "39") (pinfunction "(VSPIWP/HS2_CLK)GPIO22_39") (pintype "bidirectional"))
      (node (ref "U3") (pin "4") (pinfunction "SCL_4") (pintype "bidirectional"))
    )
    (net (code "62") (name "SCLK") (class "Default")
      (node (ref "U$1") (pin "16") (pinfunction "SCLK_16") (pintype "bidirectional"))
      (node (ref "U10") (pin "35") (pinfunction "(VSPICLK/HS1_DATA7)GPIO18_35") (pintype "bidirectional"))
    )
    (net (code "63") (name "SDA") (class "Default")
      (node (ref "R1") (pin "2") (pinfunction "2_2") (pintype "passive"))
      (node (ref "U$3") (pin "1") (pinfunction "SDA_1") (pintype "bidirectional"))
      (node (ref "U10") (pin "42") (pinfunction "(VSPIHD/HS2_CMD)GPIO21_42") (pintype "bidirectional"))
      (node (ref "U3") (pin "6") (pinfunction "SDA_6") (pintype "bidirectional"))
    )
    (net (code "64") (name "U0RXD") (class "Default")
      (node (ref "R12") (pin "1") (pinfunction "1_1") (pintype "passive"))
      (node (ref "U10") (pin "40") (pinfunction "(GPIO3/CLK_OUT2/HS2_DATA0)U0RXD_40") (pintype "bidirectional"))
    )
    (net (code "65") (name "U0TXD") (class "Default")
      (node (ref "R13") (pin "1") (pinfunction "1_1") (pintype "passive"))
      (node (ref "U10") (pin "41") (pinfunction "(GPIO1/CLK_OUT3/HS2_DATA1)U0TXD_41") (pintype "bidirectional"))
    )
    (net (code "66") (name "VBAT") (class "Default")
      (node (ref "C22") (pin "1") (pinfunction "1_1") (pintype "passive"))
      (node (ref "Q3") (pin "3") (pinfunction "D_3") (pintype "passive"))
      (node (ref "TP4") (pin "TP") (pinfunction "TP_TP") (pintype "input"))
      (node (ref "U5") (pin "3") (pinfunction "VBAT_3") (pintype "power_in"))
    )
    (net (code "67") (name "VIN") (class "Default")
      (node (ref "C19") (pin "1") (pinfunction "1_1") (pintype "passive"))
      (node (ref "D3") (pin "C") (pinfunction "C_C") (pintype "passive"))
      (node (ref "Q3") (pin "2") (pinfunction "S_2") (pintype "passive"))
      (node (ref "S1") (pin "3") (pinfunction "S_3") (pintype "passive"))
      (node (ref "U1") (pin "1") (pinfunction "IN_1") (pintype "input"))
    )
    (net (code "68") (name "VUSB") (class "Default")
      (node (ref "C12") (pin "1") (pinfunction "1_1") (pintype "passive"))
      (node (ref "C17") (pin "1") (pinfunction "1_1") (pintype "passive"))
      (node (ref "C21") (pin "1") (pinfunction "1_1") (pintype "passive"))
      (node (ref "D3") (pin "A") (pinfunction "A_A") (pintype "passive"))
      (node (ref "JP7") (pin "1") (pinfunction "VCC_1") (pintype "bidirectional"))
      (node (ref "Q3") (pin "1") (pinfunction "G_1") (pintype "passive"))
      (node (ref "R18") (pin "1") (pinfunction "1_1") (pintype "passive"))
      (node (ref "R20") (pin "2") (pinfunction "2_2") (pintype "passive"))
      (node (ref "U4") (pin "15") (pinfunction "VCC_15") (pintype "bidirectional"))
      (node (ref "U5") (pin "4") (pinfunction "VIN_4") (pintype "power_in"))
    )
    (net (code "69") (name "unconnected-(JP7-ID-Pad4)") (class "Default")
      (node (ref "JP7") (pin "4") (pinfunction "ID_4") (pintype "bidirectional"))
    )
    (net (code "70") (name "unconnected-(U1-BP-Pad4)") (class "Default")
      (node (ref "U1") (pin "4") (pinfunction "BP_4") (pintype "input"))
    )
    (net (code "71") (name "unconnected-(U3-INT2-Pad9)") (class "Default")
      (node (ref "U3") (pin "9") (pinfunction "INT2_9") (pintype "bidirectional"))
    )
    (net (code "72") (name "unconnected-(U4-CBUS0-Pad18)") (class "Default")
      (node (ref "U4") (pin "18") (pinfunction "CBUS0_18") (pintype "bidirectional"))
    )
    (net (code "73") (name "unconnected-(U4-CBUS1-Pad17)") (class "Default")
      (node (ref "U4") (pin "17") (pinfunction "CBUS1_17") (pintype "bidirectional"))
    )
    (net (code "74") (name "unconnected-(U4-CBUS2-Pad10)") (class "Default")
      (node (ref "U4") (pin "10") (pinfunction "CBUS2_10") (pintype "bidirectional"))
    )
    (net (code "75") (name "unconnected-(U4-CBUS3-Pad19)") (class "Default")
      (node (ref "U4") (pin "19") (pinfunction "CBUS3_19") (pintype "bidirectional"))
    )
    (net (code "76") (name "unconnected-(U4-~{CTS}-Pad9)") (class "Default")
      (node (ref "U4") (pin "9") (pinfunction "~{CTS}_9") (pintype "bidirectional"))
    )
    (net (code "77") (name "unconnected-(U4-~{DCD}-Pad8)") (class "Default")
      (node (ref "U4") (pin "8") (pinfunction "~{DCD}_8") (pintype "bidirectional"))
    )
    (net (code "78") (name "unconnected-(U4-~{DSR}-Pad7)") (class "Default")
      (node (ref "U4") (pin "7") (pinfunction "~{DSR}_7") (pintype "bidirectional"))
    )
    (net (code "79") (name "unconnected-(U4-~{RI}-Pad5)") (class "Default")
      (node (ref "U4") (pin "5") (pinfunction "~{RI}_5") (pintype "bidirectional"))
    )
    (net (code "80") (name "unconnected-(U10-(ADC2:0{slash}TOUCH0{slash}RTC10{slash}SPIHD)GPIO4-Pad24)") (class "Default")
      (node (ref "U10") (pin "24") (pinfunction "(ADC2:0/TOUCH0/RTC10/SPIHD)GPIO4_24") (pintype "bidirectional"))
    )
    (net (code "81") (name "unconnected-(U10-(ADC2:2{slash}TOUCH2{slash}RTC12{slash}SPIWP)GPIO2-Pad22)") (class "Default")
      (node (ref "U10") (pin "22") (pinfunction "(ADC2:2/TOUCH2/RTC12/SPIWP)GPIO2_22") (pintype "bidirectional"))
    )
    (net (code "82") (name "unconnected-(U10-(GPIO12{slash}ADC2:5{slash}TOUCH5{slash}RTC15{slash}SPIQ)MTDI-Pad18)") (class "Default")
      (node (ref "U10") (pin "18") (pinfunction "(GPIO12/ADC2:5/TOUCH5/RTC15/SPIQ)MTDI_18") (pintype "bidirectional"))
    )
    (net (code "83") (name "unconnected-(U10-(GPIO14{slash}ADC2:6{slash}TOUCH6{slash}RTC16{slash}SPICLK)MTMS-Pad17)") (class "Default")
      (node (ref "U10") (pin "17") (pinfunction "(GPIO14/ADC2:6/TOUCH6/RTC16/SPICLK)MTMS_17") (pintype "bidirectional"))
    )
    (net (code "84") (name "unconnected-(U10-(GPIO15{slash}ADC2:3{slash}TOUCH3{slash}RTC13{slash}SPICSO{slash}U0RTS)MTDO-Pad21)") (class "Default")
      (node (ref "U10") (pin "21") (pinfunction "(GPIO15/ADC2:3/TOUCH3/RTC13/SPICSO/U0RTS)MTDO_21") (pintype "bidirectional"))
    )
    (net (code "85") (name "unconnected-(U10-(HS1_DATA5)GPIO17-Pad27)") (class "Default")
      (node (ref "U10") (pin "27") (pinfunction "(HS1_DATA5)GPIO17_27") (pintype "bidirectional"))
    )
    (net (code "86") (name "unconnected-(U10-VDET_1(GPI34{slash}ADC1:6)-Pad10)") (class "Default")
      (node (ref "U10") (pin "10") (pinfunction "VDET_1(GPI34/ADC1:6)_10") (pintype "bidirectional"))
    )
    (net (code "87") (name "unconnected-(U10-VDET_2(GPI35{slash}ADC1:7)-Pad11)") (class "Default")
      (node (ref "U10") (pin "11") (pinfunction "VDET_2(GPI35/ADC1:7)_11") (pintype "bidirectional"))
    )
  )
)
